# zxmod.net
KiCad netlist of a schematic drawn in EAGLE
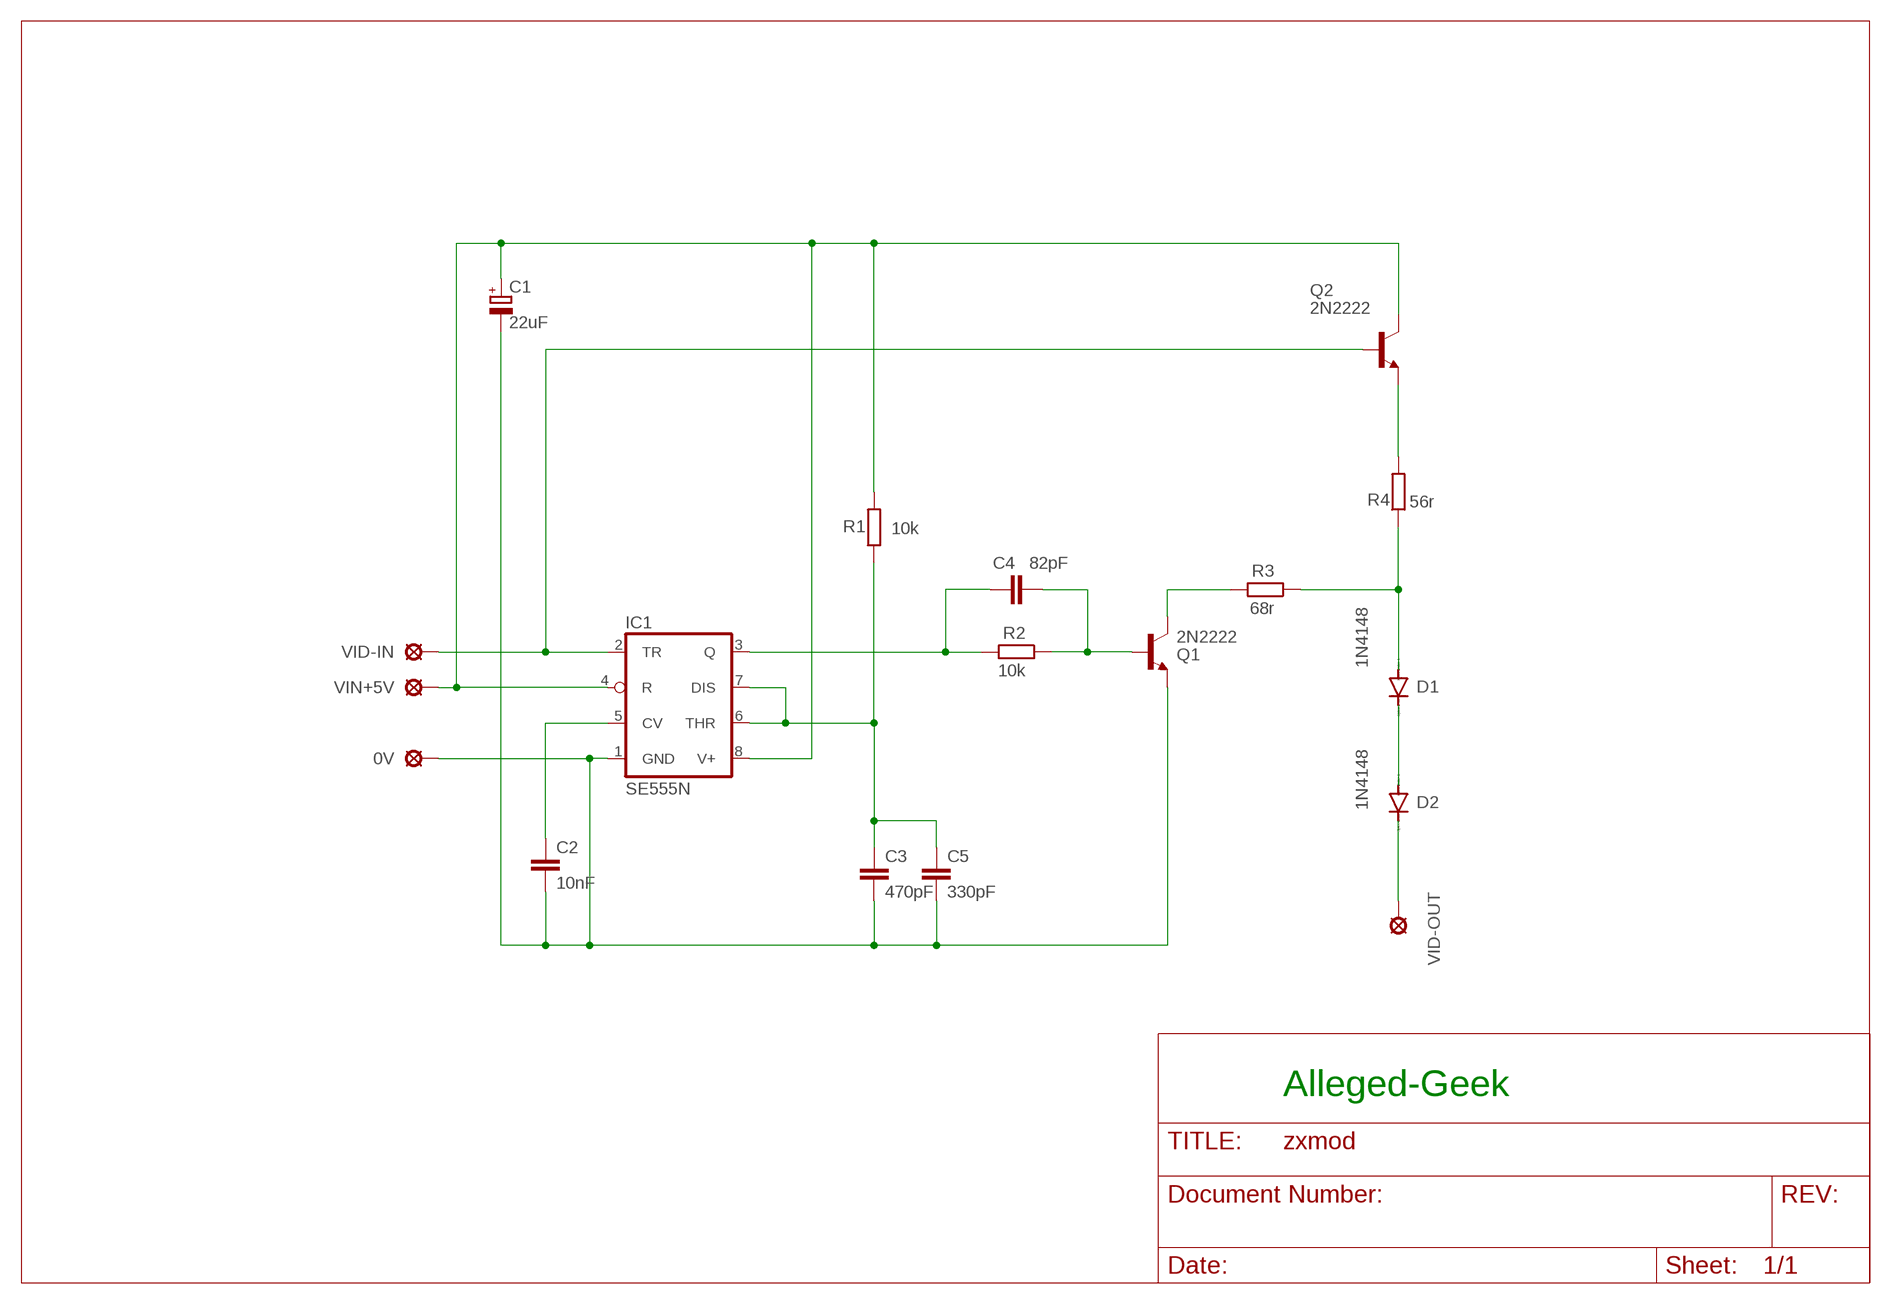
[diagram p0: schematic, sheet 1]

(export (version "E")
  (design (tool "Eeschema 10.0.6"))
  (components
    (comp (ref "0V")
      (value "LSP10")
      (footprint "eagle-import:LSP10")
      (libsource (lib "eagle-import") (part "LSP10"))
    )
    (comp (ref "C1")
      (value "22uF")
      (footprint "eagle-import:E2,5-5")
      (libsource (lib "eagle-import") (part "CPOL-EUE2.5-5"))
    )
    (comp (ref "C2")
      (value "10nF")
      (footprint "eagle-import:C050-030X075")
      (libsource (lib "eagle-import") (part "C-EU050-030X075"))
    )
    (comp (ref "C3")
      (value "470pF")
      (footprint "eagle-import:C025-024X044")
      (libsource (lib "eagle-import") (part "C-EU025-024X044"))
    )
    (comp (ref "C4")
      (value "82pF")
      (footprint "eagle-import:C025-025X050")
      (libsource (lib "eagle-import") (part "C-EU025-025X050"))
    )
    (comp (ref "C5")
      (value "330pF")
      (footprint "eagle-import:C025-024X044")
      (libsource (lib "eagle-import") (part "C-EU025-024X044"))
    )
    (comp (ref "D1")
      (value "1N4148")
      (footprint "eagle-import:DO35-7")
      (libsource (lib "eagle-import") (part "1N4148DO35-7"))
    )
    (comp (ref "D2")
      (value "1N4148")
      (footprint "eagle-import:DO35-7")
      (libsource (lib "eagle-import") (part "1N4148DO35-7"))
    )
    (comp (ref "IC1")
      (value "SE555N")
      (footprint "eagle-import:DIL08")
      (libsource (lib "eagle-import") (part "555NSE"))
    )
    (comp (ref "Q1")
      (value "2N2222")
      (footprint "eagle-import:TO18")
      (libsource (lib "eagle-import") (part "2N2222"))
    )
    (comp (ref "Q2")
      (value "2N2222")
      (footprint "eagle-import:TO18")
      (libsource (lib "eagle-import") (part "2N2222"))
    )
    (comp (ref "R1")
      (value "10k")
      (footprint "eagle-import:0207_10")
      (libsource (lib "eagle-import") (part "R-EU_0207/10"))
    )
    (comp (ref "R2")
      (value "10k")
      (footprint "eagle-import:0207_10")
      (libsource (lib "eagle-import") (part "R-EU_0207/10"))
    )
    (comp (ref "R3")
      (value "68r")
      (footprint "eagle-import:0207_10")
      (libsource (lib "eagle-import") (part "R-EU_0207/10"))
    )
    (comp (ref "R4")
      (value "56r")
      (footprint "eagle-import:0207_10")
      (libsource (lib "eagle-import") (part "R-EU_0207/10"))
    )
    (comp (ref "VID-IN")
      (value "LSP10")
      (footprint "eagle-import:LSP10")
      (libsource (lib "eagle-import") (part "LSP10"))
    )
    (comp (ref "VID-OUT")
      (value "LSP10")
      (footprint "eagle-import:LSP10")
      (libsource (lib "eagle-import") (part "LSP10"))
    )
    (comp (ref "VIN+5V")
      (value "LSP10")
      (footprint "eagle-import:LSP10")
      (libsource (lib "eagle-import") (part "LSP10"))
    )
  )
  (nets
    (net (code "1") (name "Net-(D1-PadA)") (class "Default")
      (node (ref "D1") (pin "A") (pinfunction "A_A") (pintype "passive"))
      (node (ref "R3") (pin "1") (pinfunction "1_1") (pintype "passive"))
      (node (ref "R4") (pin "1") (pinfunction "1_1") (pintype "passive"))
    )
    (net (code "2") (name "Net-(D1-PadC)") (class "Default")
      (node (ref "D1") (pin "C") (pinfunction "C_C") (pintype "passive"))
      (node (ref "D2") (pin "A") (pinfunction "A_A") (pintype "passive"))
    )
    (net (code "3") (name "Net-(D2-PadC)") (class "Default")
      (node (ref "D2") (pin "C") (pinfunction "C_C") (pintype "passive"))
      (node (ref "VID-OUT") (pin "MP") (pinfunction "MP_MP") (pintype "passive"))
    )
    (net (code "4") (name "Net-(IC1-CV)") (class "Default")
      (node (ref "C2") (pin "1") (pinfunction "1_1") (pintype "passive"))
      (node (ref "IC1") (pin "5") (pinfunction "CV_5") (pintype "input"))
    )
    (net (code "5") (name "Net-(IC1-DIS)") (class "Default")
      (node (ref "C3") (pin "1") (pinfunction "1_1") (pintype "passive"))
      (node (ref "C5") (pin "1") (pinfunction "1_1") (pintype "passive"))
      (node (ref "IC1") (pin "6") (pinfunction "THR_6") (pintype "input"))
      (node (ref "IC1") (pin "7") (pinfunction "DIS_7") (pintype "input"))
      (node (ref "R1") (pin "1") (pinfunction "1_1") (pintype "passive"))
    )
    (net (code "6") (name "Net-(IC1-GND)") (class "Default")
      (node (ref "0V") (pin "MP") (pinfunction "MP_MP") (pintype "passive"))
      (node (ref "C1") (pin "-") (pinfunction "-_-") (pintype "passive"))
      (node (ref "C2") (pin "2") (pinfunction "2_2") (pintype "passive"))
      (node (ref "C3") (pin "2") (pinfunction "2_2") (pintype "passive"))
      (node (ref "C5") (pin "2") (pinfunction "2_2") (pintype "passive"))
      (node (ref "IC1") (pin "1") (pinfunction "GND_1") (pintype "power_in"))
      (node (ref "Q1") (pin "1") (pinfunction "E_1") (pintype "passive"))
    )
    (net (code "7") (name "Net-(IC1-Q)") (class "Default")
      (node (ref "C4") (pin "1") (pinfunction "1_1") (pintype "passive"))
      (node (ref "IC1") (pin "3") (pinfunction "Q_3") (pintype "output"))
      (node (ref "R2") (pin "2") (pinfunction "2_2") (pintype "passive"))
    )
    (net (code "8") (name "Net-(IC1-R)") (class "Default")
      (node (ref "C1") (pin "+") (pinfunction "+_+") (pintype "passive"))
      (node (ref "IC1") (pin "4") (pinfunction "R_4") (pintype "input"))
      (node (ref "IC1") (pin "8") (pinfunction "V+_8") (pintype "power_in"))
      (node (ref "Q2") (pin "3") (pinfunction "C_3") (pintype "passive"))
      (node (ref "R1") (pin "2") (pinfunction "2_2") (pintype "passive"))
      (node (ref "VIN+5V") (pin "MP") (pinfunction "MP_MP") (pintype "passive"))
    )
    (net (code "9") (name "Net-(IC1-TR)") (class "Default")
      (node (ref "IC1") (pin "2") (pinfunction "TR_2") (pintype "input"))
      (node (ref "Q2") (pin "2") (pinfunction "B_2") (pintype "passive"))
      (node (ref "VID-IN") (pin "MP") (pinfunction "MP_MP") (pintype "passive"))
    )
    (net (code "10") (name "Net-(Q1-B)") (class "Default")
      (node (ref "C4") (pin "2") (pinfunction "2_2") (pintype "passive"))
      (node (ref "Q1") (pin "2") (pinfunction "B_2") (pintype "passive"))
      (node (ref "R2") (pin "1") (pinfunction "1_1") (pintype "passive"))
    )
    (net (code "11") (name "Net-(Q1-C)") (class "Default")
      (node (ref "Q1") (pin "3") (pinfunction "C_3") (pintype "passive"))
      (node (ref "R3") (pin "2") (pinfunction "2_2") (pintype "passive"))
    )
    (net (code "12") (name "Net-(Q2-E)") (class "Default")
      (node (ref "Q2") (pin "1") (pinfunction "E_1") (pintype "passive"))
      (node (ref "R4") (pin "2") (pinfunction "2_2") (pintype "passive"))
    )
  )
)
